# Isolated_DCDC.net
KiCad netlist of a schematic drawn in Altium Designer
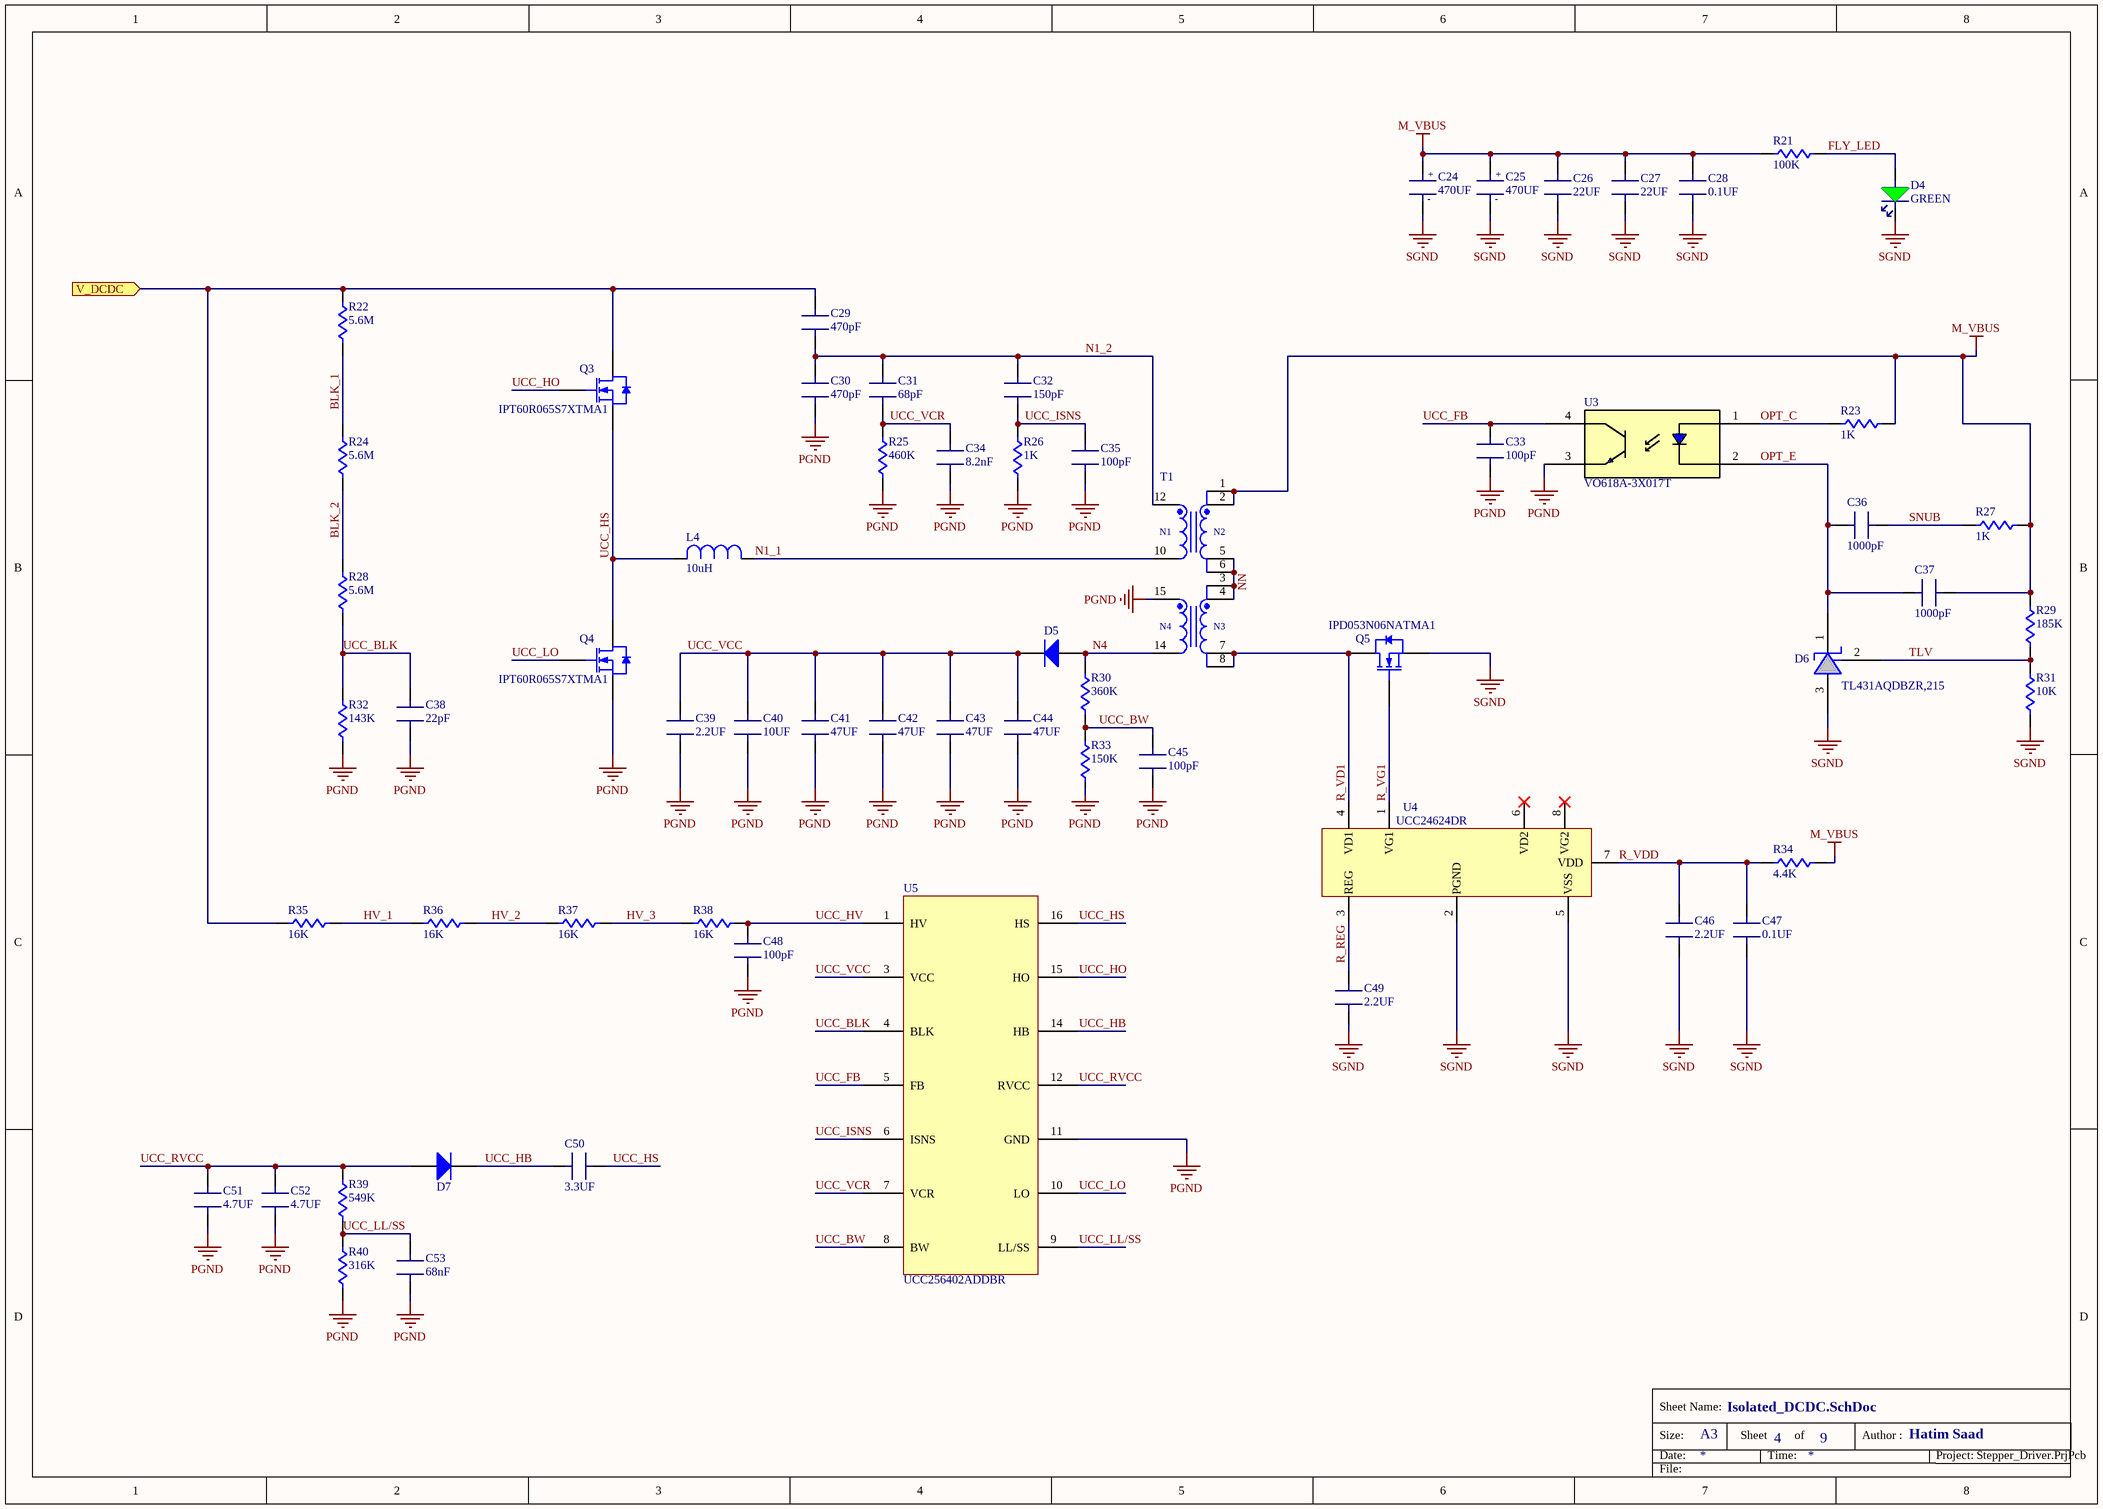
[diagram p0: Isolated_DCDC.SchDoc]

(export (version "E")
  (design (tool "Eeschema 10.0.6"))
  (components
    (comp (ref "C24")
      (value "470UF")
      (footprint "CAP: D16C7.5H25")
      (description "Aluminium Electrolytic Capacitors - Radial Leaded 100V 470uF 85C 2k Hour Radial")
      (libsource (lib "HZSchLib") (part "ESK477M100AM7AA"))
    )
    (comp (ref "C25")
      (value "470UF")
      (footprint "CAP: D16C7.5H25")
      (description "Aluminium Electrolytic Capacitors - Radial Leaded 100V 470uF 85C 2k Hour Radial")
      (libsource (lib "HZSchLib") (part "ESK477M100AM7AA"))
    )
    (comp (ref "C26")
      (value "22UF")
      (footprint "CAP: 0805")
      (description "CAP SMD 0805")
      (libsource (lib "HZSchLib") (part "CAP 0805"))
    )
    (comp (ref "C27")
      (value "22UF")
      (footprint "CAP: 0805")
      (description "CAP SMD 0805")
      (libsource (lib "HZSchLib") (part "CAP 0805"))
    )
    (comp (ref "C28")
      (value "0.1UF")
      (footprint "CAP: 0603")
      (description "CAP SMD 0603")
      (libsource (lib "HZSchLib") (part "CAP 0603"))
    )
    (comp (ref "C29")
      (value "470pF")
      (footprint "CAP: 1206")
      (description "CAP SMD 1206")
      (libsource (lib "HZSchLib") (part "CAP 1206"))
    )
    (comp (ref "C30")
      (value "470pF")
      (footprint "CAP: 1206")
      (description "CAP SMD 1206")
      (libsource (lib "HZSchLib") (part "CAP 1206"))
    )
    (comp (ref "C31")
      (value "68pF")
      (footprint "CAP: 1206")
      (description "CAP SMD 1206")
      (libsource (lib "HZSchLib") (part "CAP 1206"))
    )
    (comp (ref "C32")
      (value "150pF")
      (footprint "CAP: 1206")
      (description "CAP SMD 1206")
      (libsource (lib "HZSchLib") (part "CAP 1206"))
    )
    (comp (ref "C33")
      (value "100pF")
      (footprint "CAP: 0603")
      (description "CAP SMD 0603")
      (libsource (lib "HZSchLib") (part "CAP 0603"))
    )
    (comp (ref "C34")
      (value "8.2nF")
      (footprint "CAP: 0603")
      (description "CAP SMD 0603")
      (libsource (lib "HZSchLib") (part "CAP 0603"))
    )
    (comp (ref "C35")
      (value "100pF")
      (footprint "CAP: 0603")
      (description "CAP SMD 0603")
      (libsource (lib "HZSchLib") (part "CAP 0603"))
    )
    (comp (ref "C36")
      (value "1000pF")
      (footprint "CAP: 0603")
      (description "CAP SMD 0603")
      (libsource (lib "HZSchLib") (part "CAP 0603"))
    )
    (comp (ref "C37")
      (value "1000pF")
      (footprint "CAP: 0603")
      (description "CAP SMD 0603")
      (libsource (lib "HZSchLib") (part "CAP 0603"))
    )
    (comp (ref "C38")
      (value "22pF")
      (footprint "CAP: 0603")
      (description "CAP SMD 0603")
      (libsource (lib "HZSchLib") (part "CAP 0603"))
    )
    (comp (ref "C39")
      (value "2.2UF")
      (footprint "CAP: 0603")
      (description "CAP SMD 0603")
      (libsource (lib "HZSchLib") (part "CAP 0603"))
    )
    (comp (ref "C40")
      (value "10UF")
      (footprint "CAP: 0805")
      (description "CAP SMD 0805")
      (libsource (lib "HZSchLib") (part "CAP 0805"))
    )
    (comp (ref "C41")
      (value "47UF")
      (footprint "CAP: 1206")
      (description "CAP SMD 1206")
      (libsource (lib "Stepper_DriverSCH") (part "CAP 1206"))
    )
    (comp (ref "C42")
      (value "47UF")
      (footprint "CAP: 1206")
      (description "CAP SMD 1206")
      (libsource (lib "Stepper_DriverSCH") (part "CAP 1206"))
    )
    (comp (ref "C43")
      (value "47UF")
      (footprint "CAP: 1206")
      (description "CAP SMD 1206")
      (libsource (lib "Stepper_DriverSCH") (part "CAP 1206"))
    )
    (comp (ref "C44")
      (value "47UF")
      (footprint "CAP: 1206")
      (description "CAP SMD 1206")
      (libsource (lib "Stepper_DriverSCH") (part "CAP 1206"))
    )
    (comp (ref "C45")
      (value "100pF")
      (footprint "CAP: 0603")
      (description "CAP SMD 0603")
      (libsource (lib "HZSchLib") (part "CAP 0603"))
    )
    (comp (ref "C46")
      (value "2.2UF")
      (footprint "CAP: 0603")
      (description "CAP SMD 0603")
      (libsource (lib "HZSchLib") (part "CAP 0603"))
    )
    (comp (ref "C47")
      (value "0.1UF")
      (footprint "CAP: 0603")
      (description "CAP SMD 0603")
      (libsource (lib "HZSchLib") (part "CAP 0603"))
    )
    (comp (ref "C48")
      (value "100pF")
      (footprint "CAP: 1206")
      (description "Multilayer Ceramic Capacitors MLCC - SMD/SMT 1206 100pF 5 % 1000V NP0")
      (libsource (lib "HZSchLib") (part "VJ1206A101JXGCW1HV"))
    )
    (comp (ref "C49")
      (value "2.2UF")
      (footprint "CAP: 0603")
      (description "CAP SMD 0603")
      (libsource (lib "HZSchLib") (part "CAP 0603"))
    )
    (comp (ref "C50")
      (value "3.3UF")
      (footprint "CAP: 1206")
      (description "CAP SMD 1206")
      (libsource (lib "HZSchLib") (part "CAP 1206"))
    )
    (comp (ref "C51")
      (value "4.7UF")
      (footprint "CAP: 0603")
      (description "CAP SMD 0603")
      (libsource (lib "HZSchLib") (part "CAP 0603"))
    )
    (comp (ref "C52")
      (value "4.7UF")
      (footprint "CAP: 0603")
      (description "CAP SMD 0603")
      (libsource (lib "HZSchLib") (part "CAP 0603"))
    )
    (comp (ref "C53")
      (value "68nF")
      (footprint "CAP: 0603")
      (description "CAP SMD 0603")
      (libsource (lib "HZSchLib") (part "CAP 0603"))
    )
    (comp (ref "D4")
      (value "GREEN")
      (footprint "LED: 0603G")
      (description "LED GREEN CLEAR 0603 SMD")
      (libsource (lib "HZSchLib") (part "LED GREEN 0603"))
    )
    (comp (ref "D5")
      (value "V1PM15-M3/H")
      (footprint "DO-219AD-2")
      (description "Schottky Diodes & Rectifiers 150V 1A TMBS MicroSMP")
      (libsource (lib "HZSchLib") (part "V1PM15-M3/H"))
    )
    (comp (ref "D6")
      (value "TL431AQDBZR,215")
      (footprint "SOT23(TO-236AB)_NEX")
      (description "Shunt Voltage Reference IC Adjustable 2.495V 36 VV ±1% 100 mA TO-236AB")
      (libsource (lib "HZSchLib") (part "TL431AQDBZR,215"))
    )
    (comp (ref "D7")
      (value "V1PM15-M3/H")
      (footprint "DO-219AD-2")
      (description "Schottky Diodes & Rectifiers 150V 1A TMBS MicroSMP")
      (libsource (lib "HZSchLib") (part "V1PM15-M3/H"))
    )
    (comp (ref "L4")
      (value "10uH")
      (footprint "IND: PQ2614BLA100K")
      (description "Power Inductors - SMD 10uH 10% 30A AEC-Q200 GULL WING")
      (libsource (lib "HZSchLib") (part "PQ2614BLA-100K"))
    )
    (comp (ref "Q3")
      (value "IPT60R065S7XTMA1")
      (footprint "8-HSOF")
      (description "MOSFET N-CH 600V 8A 8HSOF")
      (libsource (lib "HZSchLib") (part "IPT60R065S7XTMA1"))
    )
    (comp (ref "Q4")
      (value "IPT60R065S7XTMA1")
      (footprint "8-HSOF")
      (description "MOSFET N-CH 600V 8A 8HSOF")
      (libsource (lib "HZSchLib") (part "IPT60R065S7XTMA1"))
    )
    (comp (ref "Q5")
      (value "IPD053N06NATMA1")
      (footprint "DPAK_3")
      (description "MOSFETs N-Ch 60V 45A DPAK-2")
      (libsource (lib "HZSchLib") (part "IPD053N06NATMA1"))
    )
    (comp (ref "R21")
      (value "100K")
      (footprint "RES: 0603")
      (description "RES SMD 0603")
      (libsource (lib "HZSchLib") (part "RES 0603"))
    )
    (comp (ref "R22")
      (value "5.6M")
      (footprint "RES: 2512")
      (description "RES SMD 2512")
      (libsource (lib "Stepper_DriverSCH") (part "RES 2512"))
    )
    (comp (ref "R23")
      (value "1K")
      (footprint "RES: 0603")
      (description "RES SMD 0603")
      (libsource (lib "HZSchLib") (part "RES 0603"))
    )
    (comp (ref "R24")
      (value "5.6M")
      (footprint "RES: 2512")
      (description "RES SMD 2512")
      (libsource (lib "Stepper_DriverSCH") (part "RES 2512"))
    )
    (comp (ref "R25")
      (value "460K")
      (footprint "RES: 0603")
      (description "RES SMD 0603")
      (libsource (lib "HZSchLib") (part "RES 0603"))
    )
    (comp (ref "R26")
      (value "1K")
      (footprint "RES: 0603")
      (description "RES SMD 0603")
      (libsource (lib "HZSchLib") (part "RES 0603"))
    )
    (comp (ref "R27")
      (value "1K")
      (footprint "RES: 0603")
      (description "RES SMD 0603")
      (libsource (lib "HZSchLib") (part "RES 0603"))
    )
    (comp (ref "R28")
      (value "5.6M")
      (footprint "RES: 2512")
      (description "RES SMD 2512")
      (libsource (lib "Stepper_DriverSCH") (part "RES 2512"))
    )
    (comp (ref "R29")
      (value "185K")
      (footprint "RES: 0603")
      (description "RES SMD 0603")
      (libsource (lib "HZSchLib") (part "RES 0603"))
    )
    (comp (ref "R30")
      (value "360K")
      (footprint "RES: 0603")
      (description "RES SMD 0603")
      (libsource (lib "HZSchLib") (part "RES 0603"))
    )
    (comp (ref "R31")
      (value "10K")
      (footprint "RES: 0603")
      (description "RES SMD 0603")
      (libsource (lib "HZSchLib") (part "RES 0603"))
    )
    (comp (ref "R32")
      (value "143K")
      (footprint "RES: 0603")
      (description "RES SMD 0603")
      (libsource (lib "HZSchLib") (part "RES 0603"))
    )
    (comp (ref "R33")
      (value "150K")
      (footprint "RES: 0603")
      (description "RES SMD 0603")
      (libsource (lib "HZSchLib") (part "RES 0603"))
    )
    (comp (ref "R34")
      (value "4.4K")
      (footprint "RES: 0603")
      (description "RES SMD 0603")
      (libsource (lib "HZSchLib") (part "RES 0603"))
    )
    (comp (ref "R35")
      (value "16K")
      (footprint "RES: 2512")
      (description "Thick Film Resistors CRCW2512 100 16K9 1% E67 e3")
      (libsource (lib "HZSchLib") (part "CRCW251216K9FKEG"))
    )
    (comp (ref "R36")
      (value "16K")
      (footprint "RES: 2512")
      (description "Thick Film Resistors CRCW2512 100 16K9 1% E67 e3")
      (libsource (lib "HZSchLib") (part "CRCW251216K9FKEG"))
    )
    (comp (ref "R37")
      (value "16K")
      (footprint "RES: 2512")
      (description "Thick Film Resistors CRCW2512 100 16K9 1% E67 e3")
      (libsource (lib "HZSchLib") (part "CRCW251216K9FKEG"))
    )
    (comp (ref "R38")
      (value "16K")
      (footprint "RES: 2512")
      (description "Thick Film Resistors CRCW2512 100 16K9 1% E67 e3")
      (libsource (lib "HZSchLib") (part "CRCW251216K9FKEG"))
    )
    (comp (ref "R39")
      (value "549K")
      (footprint "RES: 1206")
      (description "RES SMD 1206")
      (libsource (lib "HZSchLib") (part "RES 1206"))
    )
    (comp (ref "R40")
      (value "316K")
      (footprint "RES: 0603")
      (description "RES SMD 0603")
      (libsource (lib "HZSchLib") (part "RES 0603"))
    )
    (comp (ref "T1")
      (value "360-400Vin, 24Vout, 250W")
      (footprint "WE-LLCR_ETD44")
      (description "WE-LLCR Resonant Converter, THT, ETD44, 360-400Vin, 24Vout, 250W")
      (fields
        (field (name "MANUFACTURER PART NUMBER") "760895741")
        (field (name "MANUFACTURER") "Wurth Elektronik")
      )
      (libsource (lib "HZSchLib") (part "760895741"))
    )
    (comp (ref "U3")
      (value "VO618A-3X017T")
      (footprint "4-SMD_2")
      (description "Transistor Output Optocouplers Phototransistor Out CTR 100-200%")
      (libsource (lib "HZSchLib") (part "VO618A-3X017T"))
    )
    (comp (ref "U4")
      (value "UCC24624DR")
      (footprint "8-SOIC")
      (description "Gate Drivers High-frequency dual synchronous rectifi A 595-UCC24624DT")
      (libsource (lib "HZSchLib") (part "UCC24624DR"))
    )
    (comp (ref "U5")
      (value "UCC256402ADDBR")
      (footprint "14-SOIC (DDB)")
      (description "Switching Controllers LLC resonant control ler with ultra-low s A 595-UCC256402ADDBT")
      (libsource (lib "HZSchLib") (part "UCC256402ADDBR"))
    )
  )
  (nets
    (net (code "1") (name "/BLK_1") (class "Default")
      (node (ref "R22") (pin "1") (pinfunction "1_1") (pintype "passive"))
      (node (ref "R24") (pin "2") (pinfunction "2_2") (pintype "passive"))
    )
    (net (code "2") (name "/BLK_2") (class "Default")
      (node (ref "R24") (pin "1") (pinfunction "1_1") (pintype "passive"))
      (node (ref "R28") (pin "2") (pinfunction "2_2") (pintype "passive"))
    )
    (net (code "3") (name "/FLY_LED") (class "Default")
      (node (ref "D4") (pin "2") (pinfunction "A_2") (pintype "passive"))
      (node (ref "R21") (pin "1") (pinfunction "1_1") (pintype "passive"))
    )
    (net (code "4") (name "/HV_1") (class "Default")
      (node (ref "R35") (pin "2") (pinfunction "2_2") (pintype "passive"))
      (node (ref "R36") (pin "1") (pinfunction "1_1") (pintype "passive"))
    )
    (net (code "5") (name "/HV_2") (class "Default")
      (node (ref "R36") (pin "2") (pinfunction "2_2") (pintype "passive"))
      (node (ref "R37") (pin "1") (pinfunction "1_1") (pintype "passive"))
    )
    (net (code "6") (name "/HV_3") (class "Default")
      (node (ref "R37") (pin "2") (pinfunction "2_2") (pintype "passive"))
      (node (ref "R38") (pin "1") (pinfunction "1_1") (pintype "passive"))
    )
    (net (code "7") (name "/N1_1") (class "Default")
      (node (ref "L4") (pin "1") (pinfunction "1_1") (pintype "passive"))
      (node (ref "T1") (pin "10") (pinfunction "10_10") (pintype "passive"))
    )
    (net (code "8") (name "/N1_2") (class "Default")
      (node (ref "C29") (pin "1") (pinfunction "A_1") (pintype "passive"))
      (node (ref "C30") (pin "2") (pinfunction "B_2") (pintype "passive"))
      (node (ref "C31") (pin "2") (pinfunction "B_2") (pintype "passive"))
      (node (ref "C32") (pin "2") (pinfunction "B_2") (pintype "passive"))
      (node (ref "T1") (pin "12") (pinfunction "12_12") (pintype "passive"))
    )
    (net (code "9") (name "/N4") (class "Default")
      (node (ref "D5") (pin "2") (pinfunction "A_2") (pintype "passive"))
      (node (ref "R30") (pin "2") (pinfunction "2_2") (pintype "passive"))
      (node (ref "T1") (pin "14") (pinfunction "14_14") (pintype "passive"))
    )
    (net (code "10") (name "/NN") (class "Default")
      (node (ref "T1") (pin "3") (pinfunction "3_3") (pintype "passive"))
      (node (ref "T1") (pin "4") (pinfunction "4_4") (pintype "passive"))
      (node (ref "T1") (pin "5") (pinfunction "5_5") (pintype "passive"))
      (node (ref "T1") (pin "6") (pinfunction "6_6") (pintype "passive"))
    )
    (net (code "11") (name "/OPT_C") (class "Default")
      (node (ref "R23") (pin "2") (pinfunction "2_2") (pintype "passive"))
      (node (ref "U3") (pin "1") (pinfunction "A_1") (pintype "passive"))
    )
    (net (code "12") (name "/OPT_E") (class "Default")
      (node (ref "C36") (pin "2") (pinfunction "B_2") (pintype "passive"))
      (node (ref "C37") (pin "2") (pinfunction "B_2") (pintype "passive"))
      (node (ref "D6") (pin "1") (pinfunction "1_1") (pintype "passive"))
      (node (ref "U3") (pin "2") (pinfunction "C_2") (pintype "passive"))
    )
    (net (code "13") (name "/R_REG") (class "Default")
      (node (ref "C49") (pin "2") (pinfunction "B_2") (pintype "passive"))
      (node (ref "U4") (pin "3") (pinfunction "REG_3") (pintype "passive"))
    )
    (net (code "14") (name "/R_VD1") (class "Default")
      (node (ref "Q5") (pin "4") (pinfunction "D_4") (pintype "passive"))
      (node (ref "T1") (pin "7") (pinfunction "7_7") (pintype "passive"))
      (node (ref "T1") (pin "8") (pinfunction "8_8") (pintype "passive"))
      (node (ref "U4") (pin "4") (pinfunction "VD1_4") (pintype "passive"))
    )
    (net (code "15") (name "/R_VDD") (class "Default")
      (node (ref "C46") (pin "2") (pinfunction "B_2") (pintype "passive"))
      (node (ref "C47") (pin "2") (pinfunction "B_2") (pintype "passive"))
      (node (ref "R34") (pin "1") (pinfunction "1_1") (pintype "passive"))
      (node (ref "U4") (pin "7") (pinfunction "VDD_7") (pintype "passive"))
    )
    (net (code "16") (name "/R_VG1") (class "Default")
      (node (ref "Q5") (pin "1") (pinfunction "G_1") (pintype "passive"))
      (node (ref "U4") (pin "1") (pinfunction "VG1_1") (pintype "passive"))
    )
    (net (code "17") (name "/SNUB") (class "Default")
      (node (ref "C36") (pin "1") (pinfunction "A_1") (pintype "passive"))
      (node (ref "R27") (pin "2") (pinfunction "2_2") (pintype "passive"))
    )
    (net (code "18") (name "/TLV") (class "Default")
      (node (ref "D6") (pin "2") (pinfunction "2_2") (pintype "passive"))
      (node (ref "R29") (pin "2") (pinfunction "2_2") (pintype "passive"))
      (node (ref "R31") (pin "1") (pinfunction "1_1") (pintype "passive"))
    )
    (net (code "19") (name "/UCC_BLK") (class "Default")
      (node (ref "C38") (pin "2") (pinfunction "B_2") (pintype "passive"))
      (node (ref "R28") (pin "1") (pinfunction "1_1") (pintype "passive"))
      (node (ref "R32") (pin "2") (pinfunction "2_2") (pintype "passive"))
      (node (ref "U5") (pin "4") (pinfunction "BLK_4") (pintype "passive"))
    )
    (net (code "20") (name "/UCC_BW") (class "Default")
      (node (ref "C45") (pin "2") (pinfunction "B_2") (pintype "passive"))
      (node (ref "R30") (pin "1") (pinfunction "1_1") (pintype "passive"))
      (node (ref "R33") (pin "2") (pinfunction "2_2") (pintype "passive"))
      (node (ref "U5") (pin "8") (pinfunction "BW_8") (pintype "passive"))
    )
    (net (code "21") (name "/UCC_FB") (class "Default")
      (node (ref "C33") (pin "2") (pinfunction "B_2") (pintype "passive"))
      (node (ref "U3") (pin "4") (pinfunction "C_4") (pintype "passive"))
      (node (ref "U5") (pin "5") (pinfunction "FB_5") (pintype "passive"))
    )
    (net (code "22") (name "/UCC_HB") (class "Default")
      (node (ref "C50") (pin "2") (pinfunction "B_2") (pintype "passive"))
      (node (ref "D7") (pin "1") (pinfunction "K_1") (pintype "passive"))
      (node (ref "U5") (pin "14") (pinfunction "HB_14") (pintype "passive"))
    )
    (net (code "23") (name "/UCC_HO") (class "Default")
      (node (ref "Q3") (pin "1") (pinfunction "G_1") (pintype "passive"))
      (node (ref "U5") (pin "15") (pinfunction "HO_15") (pintype "passive"))
    )
    (net (code "24") (name "/UCC_HS") (class "Default")
      (node (ref "C50") (pin "1") (pinfunction "A_1") (pintype "passive"))
      (node (ref "L4") (pin "2") (pinfunction "2_2") (pintype "passive"))
      (node (ref "Q3") (pin "3") (pinfunction "S_3") (pintype "passive"))
      (node (ref "Q4") (pin "2") (pinfunction "D_2") (pintype "passive"))
      (node (ref "U5") (pin "16") (pinfunction "HS_16") (pintype "passive"))
    )
    (net (code "25") (name "/UCC_HV") (class "Default")
      (node (ref "C48") (pin "2") (pinfunction "B_2") (pintype "passive"))
      (node (ref "R38") (pin "2") (pinfunction "2_2") (pintype "passive"))
      (node (ref "U5") (pin "1") (pinfunction "HV_1") (pintype "passive"))
    )
    (net (code "26") (name "/UCC_ISNS") (class "Default")
      (node (ref "C32") (pin "1") (pinfunction "A_1") (pintype "passive"))
      (node (ref "C35") (pin "2") (pinfunction "B_2") (pintype "passive"))
      (node (ref "R26") (pin "2") (pinfunction "2_2") (pintype "passive"))
      (node (ref "U5") (pin "6") (pinfunction "ISNS_6") (pintype "passive"))
    )
    (net (code "27") (name "/UCC_LL{slash}SS") (class "Default")
      (node (ref "C53") (pin "2") (pinfunction "B_2") (pintype "passive"))
      (node (ref "R39") (pin "1") (pinfunction "1_1") (pintype "passive"))
      (node (ref "R40") (pin "2") (pinfunction "2_2") (pintype "passive"))
      (node (ref "U5") (pin "9") (pinfunction "LL/SS_9") (pintype "passive"))
    )
    (net (code "28") (name "/UCC_LO") (class "Default")
      (node (ref "Q4") (pin "1") (pinfunction "G_1") (pintype "passive"))
      (node (ref "U5") (pin "10") (pinfunction "LO_10") (pintype "passive"))
    )
    (net (code "29") (name "/UCC_RVCC") (class "Default")
      (node (ref "C51") (pin "2") (pinfunction "B_2") (pintype "passive"))
      (node (ref "C52") (pin "2") (pinfunction "B_2") (pintype "passive"))
      (node (ref "D7") (pin "2") (pinfunction "A_2") (pintype "passive"))
      (node (ref "R39") (pin "2") (pinfunction "2_2") (pintype "passive"))
      (node (ref "U5") (pin "12") (pinfunction "RVCC_12") (pintype "passive"))
    )
    (net (code "30") (name "/UCC_VCC") (class "Default")
      (node (ref "C39") (pin "2") (pinfunction "B_2") (pintype "passive"))
      (node (ref "C40") (pin "2") (pinfunction "B_2") (pintype "passive"))
      (node (ref "C41") (pin "2") (pinfunction "B_2") (pintype "passive"))
      (node (ref "C42") (pin "2") (pinfunction "B_2") (pintype "passive"))
      (node (ref "C43") (pin "2") (pinfunction "B_2") (pintype "passive"))
      (node (ref "C44") (pin "2") (pinfunction "B_2") (pintype "passive"))
      (node (ref "D5") (pin "1") (pinfunction "K_1") (pintype "passive"))
      (node (ref "U5") (pin "3") (pinfunction "VCC_3") (pintype "passive"))
    )
    (net (code "31") (name "/UCC_VCR") (class "Default")
      (node (ref "C31") (pin "1") (pinfunction "A_1") (pintype "passive"))
      (node (ref "C34") (pin "2") (pinfunction "B_2") (pintype "passive"))
      (node (ref "R25") (pin "2") (pinfunction "2_2") (pintype "passive"))
      (node (ref "U5") (pin "7") (pinfunction "VCR_7") (pintype "passive"))
    )
    (net (code "32") (name "/V_DCDC") (class "Default")
      (node (ref "C29") (pin "2") (pinfunction "B_2") (pintype "passive"))
      (node (ref "Q3") (pin "2") (pinfunction "D_2") (pintype "passive"))
      (node (ref "R22") (pin "2") (pinfunction "2_2") (pintype "passive"))
      (node (ref "R35") (pin "1") (pinfunction "1_1") (pintype "passive"))
    )
    (net (code "33") (name "M_VBUS") (class "Default")
      (node (ref "C24") (pin "1") (pinfunction "+_1") (pintype "passive"))
      (node (ref "C25") (pin "1") (pinfunction "+_1") (pintype "passive"))
      (node (ref "C26") (pin "2") (pinfunction "B_2") (pintype "passive"))
      (node (ref "C27") (pin "2") (pinfunction "B_2") (pintype "passive"))
      (node (ref "C28") (pin "2") (pinfunction "B_2") (pintype "passive"))
      (node (ref "C37") (pin "1") (pinfunction "A_1") (pintype "passive"))
      (node (ref "R21") (pin "2") (pinfunction "2_2") (pintype "passive"))
      (node (ref "R23") (pin "1") (pinfunction "1_1") (pintype "passive"))
      (node (ref "R27") (pin "1") (pinfunction "1_1") (pintype "passive"))
      (node (ref "R29") (pin "1") (pinfunction "1_1") (pintype "passive"))
      (node (ref "R34") (pin "2") (pinfunction "2_2") (pintype "passive"))
      (node (ref "T1") (pin "1") (pinfunction "1_1") (pintype "passive"))
      (node (ref "T1") (pin "2") (pinfunction "2_2") (pintype "passive"))
    )
    (net (code "34") (name "PGND") (class "Default")
      (node (ref "C30") (pin "1") (pinfunction "A_1") (pintype "passive"))
      (node (ref "C33") (pin "1") (pinfunction "A_1") (pintype "passive"))
      (node (ref "C34") (pin "1") (pinfunction "A_1") (pintype "passive"))
      (node (ref "C35") (pin "1") (pinfunction "A_1") (pintype "passive"))
      (node (ref "C38") (pin "1") (pinfunction "A_1") (pintype "passive"))
      (node (ref "C39") (pin "1") (pinfunction "A_1") (pintype "passive"))
      (node (ref "C40") (pin "1") (pinfunction "A_1") (pintype "passive"))
      (node (ref "C41") (pin "1") (pinfunction "A_1") (pintype "passive"))
      (node (ref "C42") (pin "1") (pinfunction "A_1") (pintype "passive"))
      (node (ref "C43") (pin "1") (pinfunction "A_1") (pintype "passive"))
      (node (ref "C44") (pin "1") (pinfunction "A_1") (pintype "passive"))
      (node (ref "C45") (pin "1") (pinfunction "A_1") (pintype "passive"))
      (node (ref "C48") (pin "1") (pinfunction "A_1") (pintype "passive"))
      (node (ref "C51") (pin "1") (pinfunction "A_1") (pintype "passive"))
      (node (ref "C52") (pin "1") (pinfunction "A_1") (pintype "passive"))
      (node (ref "C53") (pin "1") (pinfunction "A_1") (pintype "passive"))
      (node (ref "Q4") (pin "3") (pinfunction "S_3") (pintype "passive"))
      (node (ref "R25") (pin "1") (pinfunction "1_1") (pintype "passive"))
      (node (ref "R26") (pin "1") (pinfunction "1_1") (pintype "passive"))
      (node (ref "R32") (pin "1") (pinfunction "1_1") (pintype "passive"))
      (node (ref "R33") (pin "1") (pinfunction "1_1") (pintype "passive"))
      (node (ref "R40") (pin "1") (pinfunction "1_1") (pintype "passive"))
      (node (ref "T1") (pin "15") (pinfunction "15_15") (pintype "passive"))
      (node (ref "U3") (pin "3") (pinfunction "E_3") (pintype "passive"))
      (node (ref "U5") (pin "11") (pinfunction "GND_11") (pintype "passive"))
    )
    (net (code "35") (name "SGND") (class "Default")
      (node (ref "C24") (pin "2") (pinfunction "-_2") (pintype "passive"))
      (node (ref "C25") (pin "2") (pinfunction "-_2") (pintype "passive"))
      (node (ref "C26") (pin "1") (pinfunction "A_1") (pintype "passive"))
      (node (ref "C27") (pin "1") (pinfunction "A_1") (pintype "passive"))
      (node (ref "C28") (pin "1") (pinfunction "A_1") (pintype "passive"))
      (node (ref "C46") (pin "1") (pinfunction "A_1") (pintype "passive"))
      (node (ref "C47") (pin "1") (pinfunction "A_1") (pintype "passive"))
      (node (ref "C49") (pin "1") (pinfunction "A_1") (pintype "passive"))
      (node (ref "D4") (pin "1") (pinfunction "C_1") (pintype "passive"))
      (node (ref "D6") (pin "3") (pinfunction "3_3") (pintype "passive"))
      (node (ref "Q5") (pin "3") (pinfunction "S_3") (pintype "passive"))
      (node (ref "R31") (pin "2") (pinfunction "2_2") (pintype "passive"))
      (node (ref "U4") (pin "2") (pinfunction "PGND_2") (pintype "passive"))
      (node (ref "U4") (pin "5") (pinfunction "VSS_5") (pintype "passive"))
    )
    (net (code "36") (name "unconnected-(U4-VD2-Pad6)") (class "Default")
      (node (ref "U4") (pin "6") (pinfunction "VD2_6") (pintype "passive+no_connect"))
    )
    (net (code "37") (name "unconnected-(U4-VG2-Pad8)") (class "Default")
      (node (ref "U4") (pin "8") (pinfunction "VG2_8") (pintype "passive+no_connect"))
    )
  )
)
